# ADCduinoModule_Power.net
KiCad netlist of a schematic drawn in Altium Designer
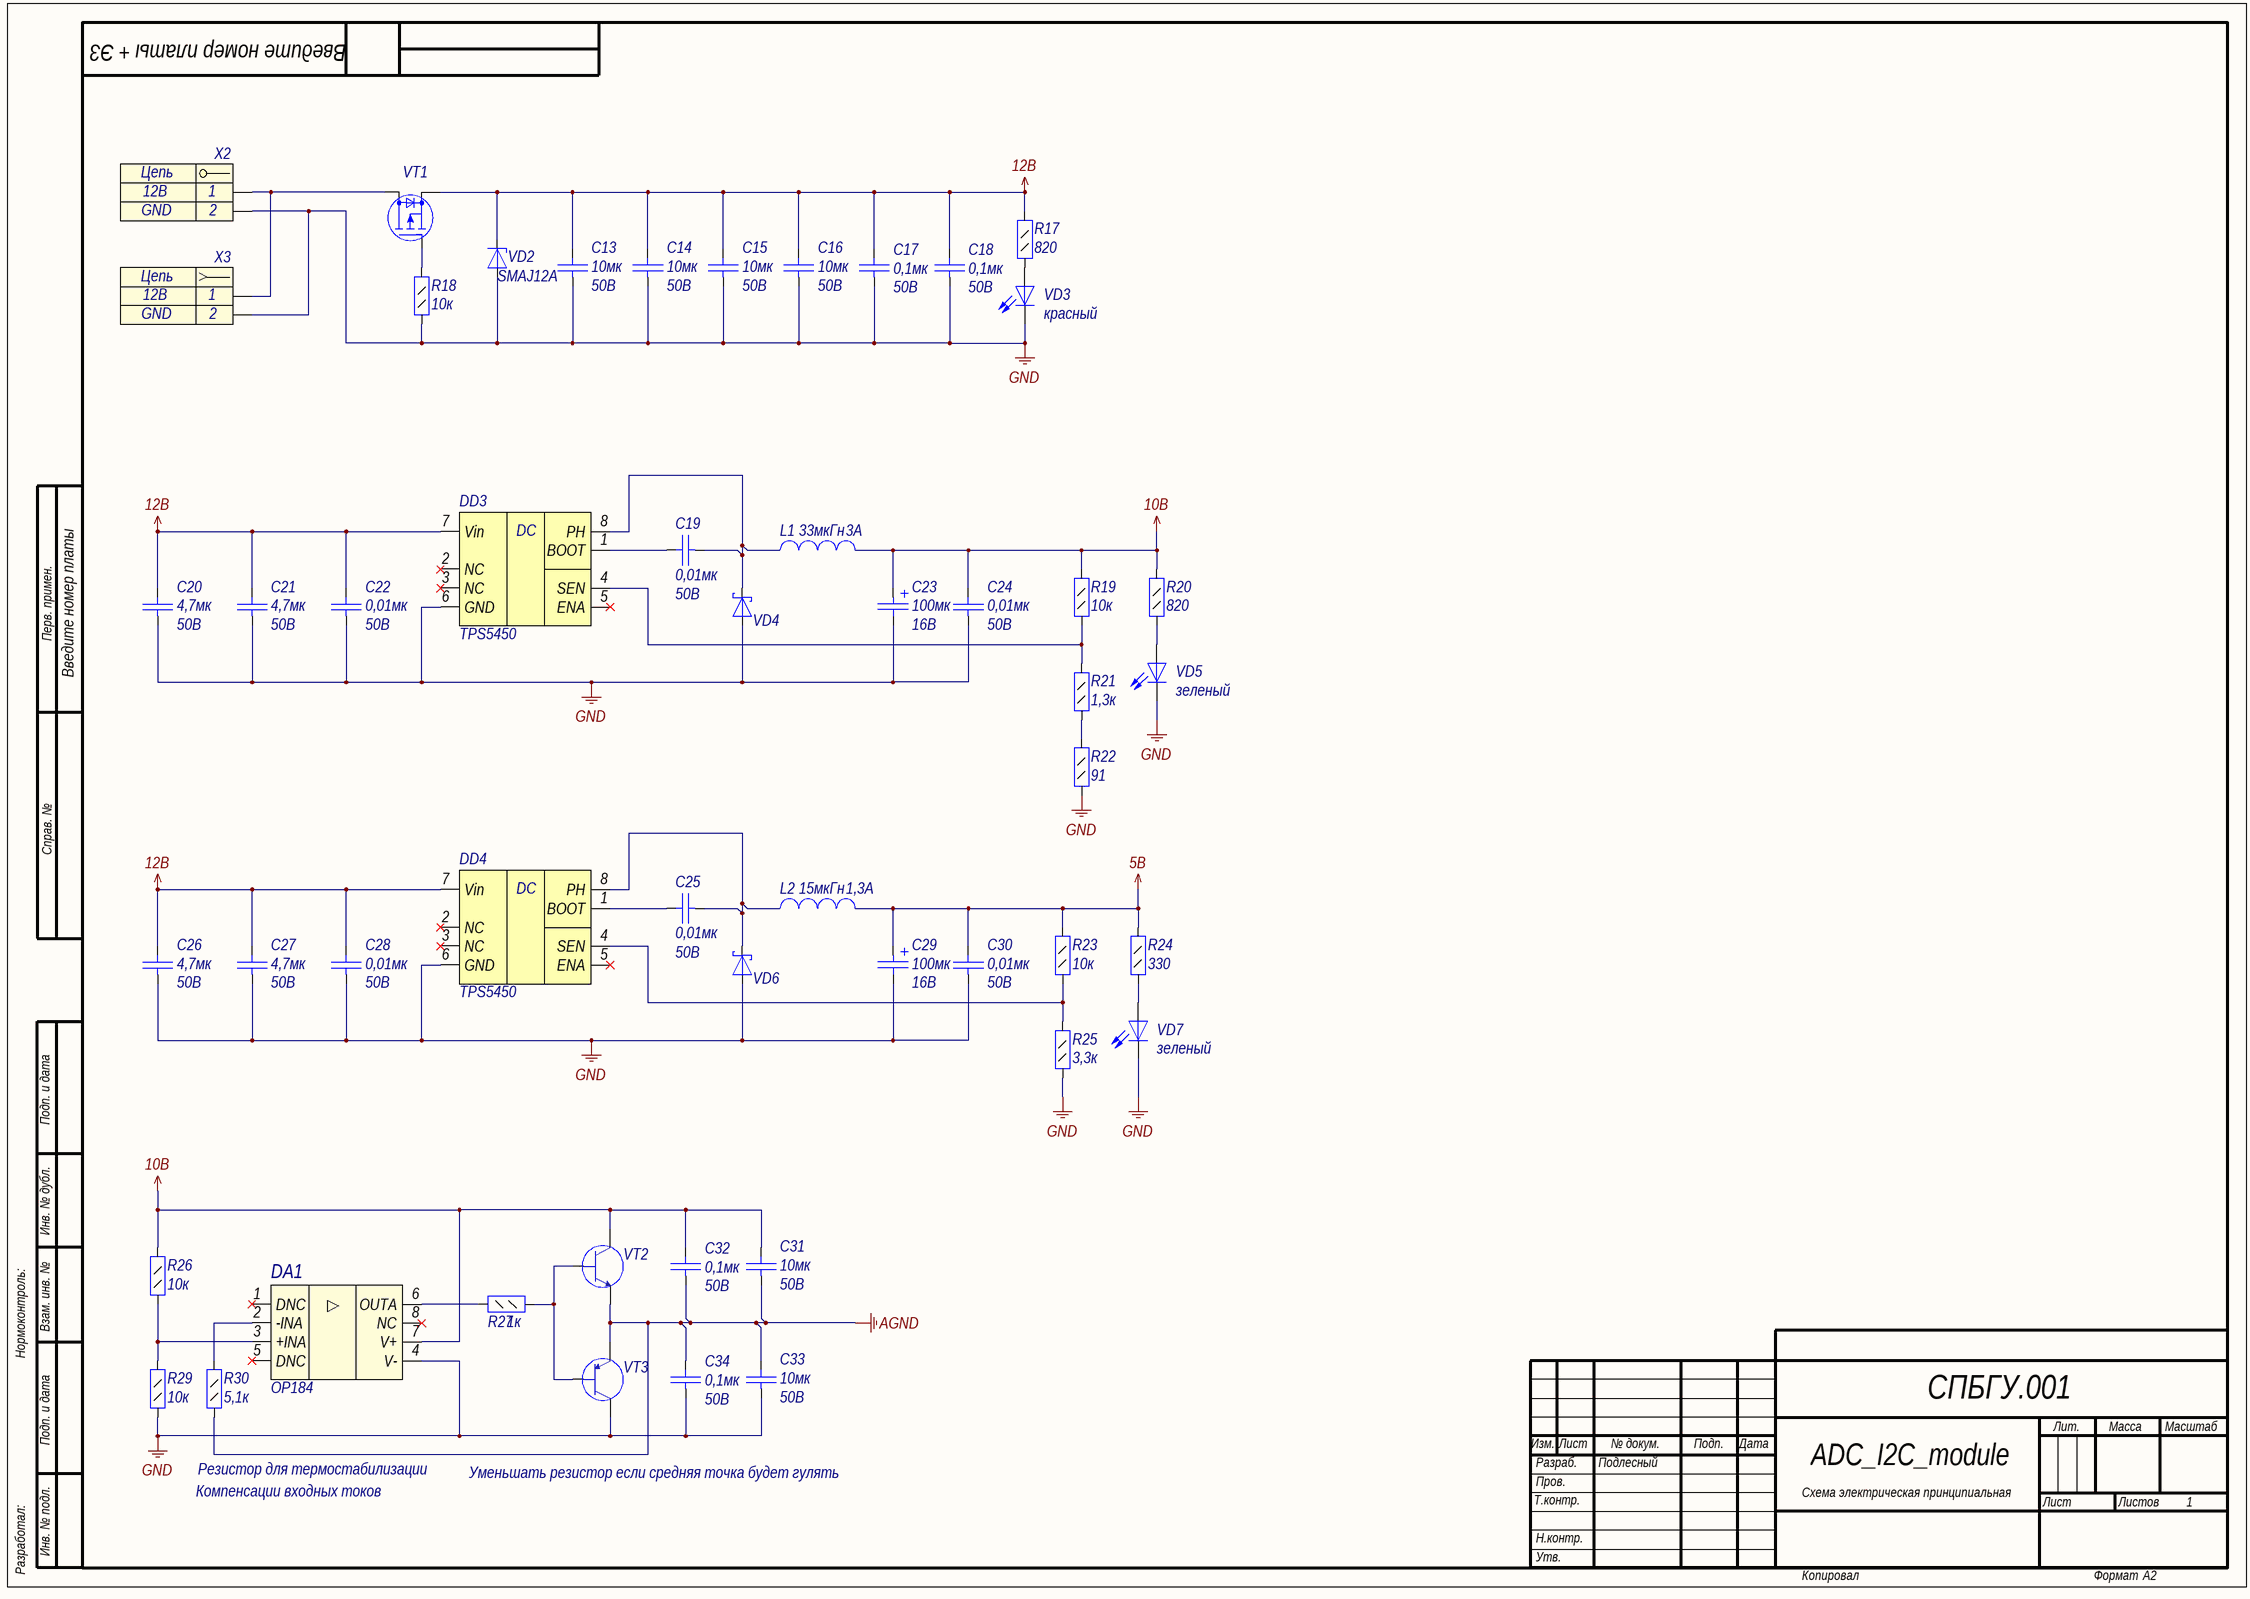
[diagram p0: ADCduinoModule_Power.SchDoc]

(export (version "E")
  (design (tool "Eeschema 10.0.6"))
  (components
    (comp (ref "C13")
      (value "10мк")
      (footprint "C1210")
      (description "Конденсатор")
      (fields
        (field (name "VOLTAGE") "50В")
        (field (name "PART NUMBER") "GRM32ER71H106K")
        (field (name "Comment") "Capacitor")
      )
      (libsource (lib "MOP44") (part "Capacitor"))
    )
    (comp (ref "C14")
      (value "10мк")
      (footprint "C1210")
      (description "Конденсатор")
      (fields
        (field (name "VOLTAGE") "50В")
        (field (name "PART NUMBER") "GRM32ER71H106K")
        (field (name "Comment") "Capacitor")
      )
      (libsource (lib "MOP44") (part "Capacitor"))
    )
    (comp (ref "C15")
      (value "10мк")
      (footprint "C1210")
      (description "Конденсатор")
      (fields
        (field (name "VOLTAGE") "50В")
        (field (name "PART NUMBER") "GRM32ER71H106K")
        (field (name "Comment") "Capacitor")
      )
      (libsource (lib "MOP44") (part "Capacitor"))
    )
    (comp (ref "C16")
      (value "10мк")
      (footprint "C1210")
      (description "Конденсатор")
      (fields
        (field (name "VOLTAGE") "50В")
        (field (name "PART NUMBER") "GRM32ER71H106K")
        (field (name "Comment") "Capacitor")
      )
      (libsource (lib "MOP44") (part "Capacitor"))
    )
    (comp (ref "C17")
      (value "0,1мк")
      (footprint "C0805")
      (description "Конденсатор")
      (fields
        (field (name "VOLTAGE") "50B")
        (field (name "PART NUMBER") "GRM21BR71H104K**")
        (field (name "Comment") "Capacitor")
      )
      (libsource (lib "MOP44") (part "Capacitor"))
    )
    (comp (ref "C18")
      (value "0,1мк")
      (footprint "C0805")
      (description "Конденсатор")
      (fields
        (field (name "VOLTAGE") "50B")
        (field (name "PART NUMBER") "GRM21BR71H104K**")
        (field (name "Comment") "Capacitor")
      )
      (libsource (lib "MOP44") (part "Capacitor"))
    )
    (comp (ref "C19")
      (value "0,01мк")
      (footprint "C0805")
      (description "Конденсатор")
      (fields
        (field (name "VOLTAGE") "50B")
        (field (name "PART NUMBER") "GRM216R71H103K")
        (field (name "Comment") "Capacitor")
      )
      (libsource (lib "MOP44") (part "Capacitor"))
    )
    (comp (ref "C20")
      (value "4,7мк")
      (footprint "C1206")
      (description "Конденсатор")
      (fields
        (field (name "VOLTAGE") "50В")
        (field (name "PART NUMBER") "GRM31CR71H475KA12L")
        (field (name "Comment") "Capacitor")
      )
      (libsource (lib "MOP44") (part "Capacitor"))
    )
    (comp (ref "C21")
      (value "4,7мк")
      (footprint "C1206")
      (description "Конденсатор")
      (fields
        (field (name "VOLTAGE") "50В")
        (field (name "PART NUMBER") "GRM31CR71H475KA12L")
        (field (name "Comment") "Capacitor")
      )
      (libsource (lib "MOP44") (part "Capacitor"))
    )
    (comp (ref "C22")
      (value "0,01мк")
      (footprint "C0805")
      (description "Конденсатор")
      (fields
        (field (name "VOLTAGE") "50B")
        (field (name "PART NUMBER") "GRM216R71H103K")
        (field (name "Comment") "Capacitor")
      )
      (libsource (lib "MOP44") (part "Capacitor"))
    )
    (comp (ref "C23")
      (value "100мк")
      (footprint "TANTAL CASE D")
      (description "Конденсатор полярный")
      (fields
        (field (name "VOLTAGE") "16В")
        (field (name "PART NUMBER") "293D107X9016D2TE3")
        (field (name "Comment") "Capacitor_pol")
      )
      (libsource (lib "MOP44") (part "Capacitor_pol"))
    )
    (comp (ref "C24")
      (value "0,01мк")
      (footprint "C0805")
      (description "Конденсатор")
      (fields
        (field (name "VOLTAGE") "50B")
        (field (name "PART NUMBER") "GRM216R71H103K")
        (field (name "Comment") "Capacitor")
      )
      (libsource (lib "MOP44") (part "Capacitor"))
    )
    (comp (ref "C25")
      (value "0,01мк")
      (footprint "C0805")
      (description "Конденсатор")
      (fields
        (field (name "VOLTAGE") "50B")
        (field (name "PART NUMBER") "GRM216R71H103K")
        (field (name "Comment") "Capacitor")
      )
      (libsource (lib "MOP44") (part "Capacitor"))
    )
    (comp (ref "C26")
      (value "4,7мк")
      (footprint "C1206")
      (description "Конденсатор")
      (fields
        (field (name "VOLTAGE") "50В")
        (field (name "PART NUMBER") "GRM31CR71H475KA12L")
        (field (name "Comment") "Capacitor")
      )
      (libsource (lib "MOP44") (part "Capacitor"))
    )
    (comp (ref "C27")
      (value "4,7мк")
      (footprint "C1206")
      (description "Конденсатор")
      (fields
        (field (name "VOLTAGE") "50В")
        (field (name "PART NUMBER") "GRM31CR71H475KA12L")
        (field (name "Comment") "Capacitor")
      )
      (libsource (lib "MOP44") (part "Capacitor"))
    )
    (comp (ref "C28")
      (value "0,01мк")
      (footprint "C0805")
      (description "Конденсатор")
      (fields
        (field (name "VOLTAGE") "50B")
        (field (name "PART NUMBER") "GRM216R71H103K")
        (field (name "Comment") "Capacitor")
      )
      (libsource (lib "MOP44") (part "Capacitor"))
    )
    (comp (ref "C29")
      (value "100мк")
      (footprint "TANTAL CASE D")
      (description "Конденсатор полярный")
      (fields
        (field (name "VOLTAGE") "16В")
        (field (name "PART NUMBER") "293D107X9016D2TE3")
        (field (name "Comment") "Capacitor_pol")
      )
      (libsource (lib "MOP44") (part "Capacitor_pol"))
    )
    (comp (ref "C30")
      (value "0,01мк")
      (footprint "C0805")
      (description "Конденсатор")
      (fields
        (field (name "VOLTAGE") "50B")
        (field (name "PART NUMBER") "GRM216R71H103K")
        (field (name "Comment") "Capacitor")
      )
      (libsource (lib "MOP44") (part "Capacitor"))
    )
    (comp (ref "C31")
      (value "10мк")
      (footprint "C1210")
      (description "Конденсатор")
      (fields
        (field (name "VOLTAGE") "50В")
        (field (name "PART NUMBER") "GRM32ER71H106K")
        (field (name "Comment") "Capacitor")
      )
      (libsource (lib "MOP44") (part "Capacitor"))
    )
    (comp (ref "C32")
      (value "0,1мк")
      (footprint "C0805")
      (description "Конденсатор")
      (fields
        (field (name "VOLTAGE") "50B")
        (field (name "PART NUMBER") "GRM21BR71H104K**")
        (field (name "Comment") "Capacitor")
      )
      (libsource (lib "MOP44") (part "Capacitor"))
    )
    (comp (ref "C33")
      (value "10мк")
      (footprint "C1210")
      (description "Конденсатор")
      (fields
        (field (name "VOLTAGE") "50В")
        (field (name "PART NUMBER") "GRM32ER71H106K")
        (field (name "Comment") "Capacitor")
      )
      (libsource (lib "MOP44") (part "Capacitor"))
    )
    (comp (ref "C34")
      (value "0,1мк")
      (footprint "C0805")
      (description "Конденсатор")
      (fields
        (field (name "VOLTAGE") "50B")
        (field (name "PART NUMBER") "GRM21BR71H104K**")
        (field (name "Comment") "Capacitor")
      )
      (libsource (lib "MOP44") (part "Capacitor"))
    )
    (comp (ref "DA1")
      (value "OP184")
      (footprint "SO8")
      (description "Precision Rail-to-Rail\r\nInput and Output Operational Amplifiers")
      (fields (field (name "PART NUMBER") "OP184ESZ"))
      (libsource (lib "MOP44") (part "OP184"))
    )
    (comp (ref "DD3")
      (value "TPS5450")
      (footprint "SO Powerpad8")
      (description "5-A, Wide Input Range, Step-Down Converter")
      (fields (field (name "MANUFACTURER") "Texas Instruments"))
      (libsource (lib "MOP44") (part "TPS5450"))
    )
    (comp (ref "DD4")
      (value "TPS5450")
      (footprint "SO Powerpad8")
      (description "5-A, Wide Input Range, Step-Down Converter")
      (fields (field (name "MANUFACTURER") "Texas Instruments"))
      (libsource (lib "MOP44") (part "TPS5450"))
    )
    (comp (ref "L1")
      (value "33мкГн")
      (footprint "IND_12.8x12.8")
      (description "EMI Suppression Filter")
      (fields
        (field (name "RATED CURRENT") "3A")
        (field (name "PART NUMBER") "B82477G4333M000")
        (field (name "Comment") "Inductor")
      )
      (libsource (lib "MOP44") (part "Inductor"))
    )
    (comp (ref "L2")
      (value "15мкГн")
      (footprint "SDR0604")
      (description "EMI Suppression Filter")
      (fields
        (field (name "RATED CURRENT") "1,3A")
        (field (name "PART NUMBER") "SDR0604- 150YL")
        (field (name "Comment") "Inductor")
      )
      (libsource (lib "MOP44") (part "Inductor"))
    )
    (comp (ref "R17")
      (value "820")
      (footprint "R0805")
      (description "Резистор")
      (fields (field (name "PART NUMBER") "RC0805FR-07820RL") (field (name "POWER") "0,125Вт"))
      (libsource (lib "MOP44") (part "Resistor_0,125Вт"))
    )
    (comp (ref "R18")
      (value "10к")
      (footprint "R0805")
      (description "Резистор")
      (fields (field (name "PART NUMBER") "RC0805FR-0710KL") (field (name "POWER") "0,125Вт"))
      (libsource (lib "MOP44") (part "Resistor_0,125Вт"))
    )
    (comp (ref "R19")
      (value "10к")
      (footprint "R0805")
      (description "Резистор")
      (fields (field (name "PART NUMBER") "RC0805FR-0710KL") (field (name "POWER") "0,125Вт"))
      (libsource (lib "MOP44") (part "Resistor_0,125Вт"))
    )
    (comp (ref "R20")
      (value "820")
      (footprint "R0805")
      (description "Резистор")
      (fields (field (name "PART NUMBER") "RC0805FR-07820RL") (field (name "POWER") "0,125Вт"))
      (libsource (lib "MOP44") (part "Resistor_0,125Вт"))
    )
    (comp (ref "R21")
      (value "1,3к")
      (footprint "R0805")
      (description "Резистор")
      (fields (field (name "PART NUMBER") "RC0805FR-071K3") (field (name "POWER") "0,125Вт"))
      (libsource (lib "MOP44") (part "Resistor_0,125Вт"))
    )
    (comp (ref "R22")
      (value "91")
      (footprint "R0805")
      (description "Резистор")
      (fields (field (name "PART NUMBER") "RC0805FR-0791RL") (field (name "POWER") "0,125Вт"))
      (libsource (lib "MOP44") (part "Resistor_0,125Вт"))
    )
    (comp (ref "R23")
      (value "10к")
      (footprint "R0805")
      (description "Резистор")
      (fields (field (name "PART NUMBER") "RC0805FR-0710KL") (field (name "POWER") "0,125Вт"))
      (libsource (lib "MOP44") (part "Resistor_0,125Вт"))
    )
    (comp (ref "R24")
      (value "330")
      (footprint "R0805")
      (description "Резистор")
      (fields (field (name "PART NUMBER") "RC0805FR-07330RL") (field (name "POWER") "0,125Вт"))
      (libsource (lib "MOP44") (part "Resistor_0,125Вт"))
    )
    (comp (ref "R25")
      (value "3,3к")
      (footprint "R0805")
      (description "Резистор")
      (fields (field (name "PART NUMBER") "RC0805FR-072K3") (field (name "POWER") "0,125Вт"))
      (libsource (lib "MOP44") (part "Resistor_0,125Вт"))
    )
    (comp (ref "R26")
      (value "10к")
      (footprint "R0805")
      (description "Резистор")
      (fields (field (name "PART NUMBER") "RC0805FR-0710KL") (field (name "POWER") "0,125Вт"))
      (libsource (lib "MOP44") (part "Resistor_0,125Вт"))
    )
    (comp (ref "R27")
      (value "1к")
      (footprint "R0805")
      (description "Резистор")
      (fields (field (name "PART NUMBER") "RC0805FR-071KL") (field (name "POWER") "0,125Вт"))
      (libsource (lib "") (part "Resistor_0,125Вт_1"))
    )
    (comp (ref "R29")
      (value "10к")
      (footprint "R0805")
      (description "Резистор")
      (fields (field (name "PART NUMBER") "RC0805FR-0710KL") (field (name "POWER") "0,125Вт"))
      (libsource (lib "MOP44") (part "Resistor_0,125Вт"))
    )
    (comp (ref "R30")
      (value "5,1к")
      (footprint "R0805")
      (description "Резистор")
      (fields (field (name "PART NUMBER") "RC0805FR-075K1") (field (name "POWER") "0,125Вт"))
      (libsource (lib "MOP44") (part "Resistor_0,125Вт"))
    )
    (comp (ref "VD2")
      (value "DiodeZener")
      (footprint "SMA")
      (description "Cтабилитрон (лавинный выпрямительный диод) односторонний")
      (fields (field (name "PART NUMBER") "SMAJ12A"))
      (libsource (lib "MOP44") (part "DiodeZener"))
    )
    (comp (ref "VD3")
      (value "красный")
      (footprint "L_0805")
      (description "Светодиод")
      (fields (field (name "PART NUMBER") "KP-2012EC"))
      (libsource (lib "MOP44") (part "LED"))
    )
    (comp (ref "VD4")
      (value "DiodeSchottky")
      (footprint "SMA")
      (description "Диод Шоттки")
      (fields (field (name "PART NUMBER") "SK34A"))
      (libsource (lib "MOP44") (part "DiodeSchottky"))
    )
    (comp (ref "VD5")
      (value "зеленый")
      (footprint "L_0805")
      (description "Светодиод")
      (fields (field (name "PART NUMBER") "KP-2012MGC"))
      (libsource (lib "MOP44") (part "LED"))
    )
    (comp (ref "VD6")
      (value "DiodeSchottky")
      (footprint "SMA")
      (description "Диод Шоттки")
      (fields (field (name "PART NUMBER") "SK34A"))
      (libsource (lib "MOP44") (part "DiodeSchottky"))
    )
    (comp (ref "VD7")
      (value "зеленый")
      (footprint "L_0805")
      (description "Светодиод")
      (fields (field (name "PART NUMBER") "KP-2012MGC"))
      (libsource (lib "MOP44") (part "LED"))
    )
    (comp (ref "VT1")
      (value "P-MOSFET")
      (footprint "DPAK")
      (description "N-MOSFET")
      (fields (field (name "PART NUMBER") "FDD6637") (field (name "MANUFACTURER") "Fairchild Semiconductor"))
      (libsource (lib "MOP44") (part "P-MOSFET"))
    )
    (comp (ref "VT2")
      (value "BJT NPN")
      (footprint "SOT-223")
      (fields (field (name "POWER") "2Вт") (field (name "PART NUMBER") "PBSS4540Z.115"))
      (libsource (lib "MOP44") (part "BJT NPN"))
    )
    (comp (ref "VT3")
      (value "BJT PNP")
      (footprint "SOT-223")
      (fields (field (name "POWER") "2Вт") (field (name "PART NUMBER") "PBSS5540Z.115"))
      (libsource (lib "MOP44") (part "BJT PNP"))
    )
    (comp (ref "X2")
      (value "Header_2_trm")
      (footprint "TERMINAL-2WAY-3.5MM")
      (description "Разъем - 2 конт. клеммник")
      (libsource (lib "MOP44") (part "Header_2_trm"))
    )
    (comp (ref "X3")
      (value "Header_2_sct")
      (footprint "DS-210")
      (description "Разъем - 2 конт. розетка")
      (fields (field (name "PART NUMBER") "DS-210B(PBT)(NB)"))
      (libsource (lib "MOP44") (part "Header_2_sct"))
    )
  )
  (nets
    (net (code "1") (name "5B") (class "Default")
      (node (ref "C29") (pin "1") (pinfunction "1_1") (pintype "passive"))
      (node (ref "C30") (pin "2") (pinfunction "2_2") (pintype "passive"))
      (node (ref "L2") (pin "2") (pinfunction "2_2") (pintype "passive"))
      (node (ref "R23") (pin "2") (pinfunction "2_2") (pintype "passive"))
      (node (ref "R24") (pin "2") (pinfunction "2_2") (pintype "passive"))
    )
    (net (code "2") (name "10B") (class "Default")
      (node (ref "C23") (pin "1") (pinfunction "1_1") (pintype "passive"))
      (node (ref "C24") (pin "2") (pinfunction "2_2") (pintype "passive"))
      (node (ref "C31") (pin "2") (pinfunction "2_2") (pintype "passive"))
      (node (ref "C32") (pin "2") (pinfunction "2_2") (pintype "passive"))
      (node (ref "DA1") (pin "7") (pinfunction "V+_7") (pintype "power_in"))
      (node (ref "L1") (pin "2") (pinfunction "2_2") (pintype "passive"))
      (node (ref "R19") (pin "2") (pinfunction "2_2") (pintype "passive"))
      (node (ref "R20") (pin "2") (pinfunction "2_2") (pintype "passive"))
      (node (ref "R26") (pin "2") (pinfunction "2_2") (pintype "passive"))
      (node (ref "VT2") (pin "3") (pinfunction "3_3") (pintype "passive"))
    )
    (net (code "3") (name "12B") (class "Default")
      (node (ref "C13") (pin "2") (pinfunction "2_2") (pintype "passive"))
      (node (ref "C14") (pin "2") (pinfunction "2_2") (pintype "passive"))
      (node (ref "C15") (pin "2") (pinfunction "2_2") (pintype "passive"))
      (node (ref "C16") (pin "2") (pinfunction "2_2") (pintype "passive"))
      (node (ref "C17") (pin "2") (pinfunction "2_2") (pintype "passive"))
      (node (ref "C18") (pin "2") (pinfunction "2_2") (pintype "passive"))
      (node (ref "C20") (pin "2") (pinfunction "2_2") (pintype "passive"))
      (node (ref "C21") (pin "2") (pinfunction "2_2") (pintype "passive"))
      (node (ref "C22") (pin "2") (pinfunction "2_2") (pintype "passive"))
      (node (ref "C26") (pin "2") (pinfunction "2_2") (pintype "passive"))
      (node (ref "C27") (pin "2") (pinfunction "2_2") (pintype "passive"))
      (node (ref "C28") (pin "2") (pinfunction "2_2") (pintype "passive"))
      (node (ref "DD3") (pin "7") (pinfunction "Vin_7") (pintype "passive"))
      (node (ref "DD4") (pin "7") (pinfunction "Vin_7") (pintype "passive"))
      (node (ref "R17") (pin "2") (pinfunction "2_2") (pintype "passive"))
      (node (ref "VD2") (pin "1") (pinfunction "K_1") (pintype "passive"))
      (node (ref "VT1") (pin "3") (pinfunction "S_3") (pintype "passive"))
    )
    (net (code "4") (name "AGND") (class "Default")
      (node (ref "C31") (pin "1") (pinfunction "1_1") (pintype "passive"))
      (node (ref "C32") (pin "1") (pinfunction "1_1") (pintype "passive"))
      (node (ref "C33") (pin "2") (pinfunction "2_2") (pintype "passive"))
      (node (ref "C34") (pin "2") (pinfunction "2_2") (pintype "passive"))
      (node (ref "R30") (pin "1") (pinfunction "1_1") (pintype "passive"))
      (node (ref "VT2") (pin "2") (pinfunction "2_2") (pintype "passive"))
      (node (ref "VT3") (pin "2") (pinfunction "2_2") (pintype "passive"))
    )
    (net (code "5") (name "GND") (class "Default")
      (node (ref "C13") (pin "1") (pinfunction "1_1") (pintype "passive"))
      (node (ref "C14") (pin "1") (pinfunction "1_1") (pintype "passive"))
      (node (ref "C15") (pin "1") (pinfunction "1_1") (pintype "passive"))
      (node (ref "C16") (pin "1") (pinfunction "1_1") (pintype "passive"))
      (node (ref "C17") (pin "1") (pinfunction "1_1") (pintype "passive"))
      (node (ref "C18") (pin "1") (pinfunction "1_1") (pintype "passive"))
      (node (ref "C20") (pin "1") (pinfunction "1_1") (pintype "passive"))
      (node (ref "C21") (pin "1") (pinfunction "1_1") (pintype "passive"))
      (node (ref "C22") (pin "1") (pinfunction "1_1") (pintype "passive"))
      (node (ref "C23") (pin "2") (pinfunction "2_2") (pintype "passive"))
      (node (ref "C24") (pin "1") (pinfunction "1_1") (pintype "passive"))
      (node (ref "C26") (pin "1") (pinfunction "1_1") (pintype "passive"))
      (node (ref "C27") (pin "1") (pinfunction "1_1") (pintype "passive"))
      (node (ref "C28") (pin "1") (pinfunction "1_1") (pintype "passive"))
      (node (ref "C29") (pin "2") (pinfunction "2_2") (pintype "passive"))
      (node (ref "C30") (pin "1") (pinfunction "1_1") (pintype "passive"))
      (node (ref "C33") (pin "1") (pinfunction "1_1") (pintype "passive"))
      (node (ref "C34") (pin "1") (pinfunction "1_1") (pintype "passive"))
      (node (ref "DA1") (pin "4") (pinfunction "V-_4") (pintype "power_in"))
      (node (ref "DD3") (pin "6") (pinfunction "GND_6") (pintype "passive"))
      (node (ref "DD4") (pin "6") (pinfunction "GND_6") (pintype "passive"))
      (node (ref "R18") (pin "1") (pinfunction "1_1") (pintype "passive"))
      (node (ref "R22") (pin "1") (pinfunction "1_1") (pintype "passive"))
      (node (ref "R25") (pin "1") (pinfunction "1_1") (pintype "passive"))
      (node (ref "R29") (pin "1") (pinfunction "1_1") (pintype "passive"))
      (node (ref "VD2") (pin "2") (pinfunction "A_2") (pintype "passive"))
      (node (ref "VD3") (pin "1") (pinfunction "K_1") (pintype "passive"))
      (node (ref "VD4") (pin "2") (pinfunction "A_2") (pintype "passive"))
      (node (ref "VD5") (pin "1") (pinfunction "K_1") (pintype "passive"))
      (node (ref "VD6") (pin "2") (pinfunction "A_2") (pintype "passive"))
      (node (ref "VD7") (pin "1") (pinfunction "K_1") (pintype "passive"))
      (node (ref "VT3") (pin "3") (pinfunction "3_3") (pintype "passive"))
      (node (ref "X2") (pin "2") (pinfunction "2_2") (pintype "passive"))
      (node (ref "X3") (pin "2") (pinfunction "2_2") (pintype "passive"))
    )
    (net (code "6") (name "Net-(DA1-+INA)") (class "Default")
      (node (ref "DA1") (pin "3") (pinfunction "+INA_3") (pintype "power_in"))
      (node (ref "R26") (pin "1") (pinfunction "1_1") (pintype "passive"))
      (node (ref "R29") (pin "2") (pinfunction "2_2") (pintype "passive"))
    )
    (net (code "7") (name "Net-(DA1--INA)") (class "Default")
      (node (ref "DA1") (pin "2") (pinfunction "-INA_2") (pintype "power_in"))
      (node (ref "R30") (pin "2") (pinfunction "2_2") (pintype "passive"))
    )
    (net (code "8") (name "Net-(DA1-OUTA)") (class "Default")
      (node (ref "DA1") (pin "6") (pinfunction "OUTA_6") (pintype "power_in"))
      (node (ref "R27") (pin "1") (pinfunction "1_1") (pintype "passive"))
    )
    (net (code "9") (name "Net-(DD3-BOOT)") (class "Default")
      (node (ref "C19") (pin "2") (pinfunction "2_2") (pintype "passive"))
      (node (ref "DD3") (pin "1") (pinfunction "BOOT_1") (pintype "passive"))
    )
    (net (code "10") (name "Net-(DD3-PH)") (class "Default")
      (node (ref "C19") (pin "1") (pinfunction "1_1") (pintype "passive"))
      (node (ref "DD3") (pin "8") (pinfunction "PH_8") (pintype "passive"))
      (node (ref "L1") (pin "1") (pinfunction "1_1") (pintype "passive"))
      (node (ref "VD4") (pin "1") (pinfunction "K_1") (pintype "passive"))
    )
    (net (code "11") (name "Net-(DD3-SEN)") (class "Default")
      (node (ref "DD3") (pin "4") (pinfunction "SEN_4") (pintype "passive"))
      (node (ref "R19") (pin "1") (pinfunction "1_1") (pintype "passive"))
      (node (ref "R21") (pin "2") (pinfunction "2_2") (pintype "passive"))
    )
    (net (code "12") (name "Net-(DD4-BOOT)") (class "Default")
      (node (ref "C25") (pin "2") (pinfunction "2_2") (pintype "passive"))
      (node (ref "DD4") (pin "1") (pinfunction "BOOT_1") (pintype "passive"))
    )
    (net (code "13") (name "Net-(DD4-PH)") (class "Default")
      (node (ref "C25") (pin "1") (pinfunction "1_1") (pintype "passive"))
      (node (ref "DD4") (pin "8") (pinfunction "PH_8") (pintype "passive"))
      (node (ref "L2") (pin "1") (pinfunction "1_1") (pintype "passive"))
      (node (ref "VD6") (pin "1") (pinfunction "K_1") (pintype "passive"))
    )
    (net (code "14") (name "Net-(DD4-SEN)") (class "Default")
      (node (ref "DD4") (pin "4") (pinfunction "SEN_4") (pintype "passive"))
      (node (ref "R23") (pin "1") (pinfunction "1_1") (pintype "passive"))
      (node (ref "R25") (pin "2") (pinfunction "2_2") (pintype "passive"))
    )
    (net (code "15") (name "Net-(R21-Pad1)") (class "Default")
      (node (ref "R21") (pin "1") (pinfunction "1_1") (pintype "passive"))
      (node (ref "R22") (pin "2") (pinfunction "2_2") (pintype "passive"))
    )
    (net (code "16") (name "Net-(R27-Pad2)") (class "Default")
      (node (ref "R27") (pin "2") (pinfunction "2_2") (pintype "passive"))
      (node (ref "VT2") (pin "1") (pinfunction "1_1") (pintype "passive"))
      (node (ref "VT3") (pin "1") (pinfunction "1_1") (pintype "passive"))
    )
    (net (code "17") (name "Net-(VD3-A)") (class "Default")
      (node (ref "R17") (pin "1") (pinfunction "1_1") (pintype "passive"))
      (node (ref "VD3") (pin "2") (pinfunction "A_2") (pintype "passive"))
    )
    (net (code "18") (name "Net-(VD5-A)") (class "Default")
      (node (ref "R20") (pin "1") (pinfunction "1_1") (pintype "passive"))
      (node (ref "VD5") (pin "2") (pinfunction "A_2") (pintype "passive"))
    )
    (net (code "19") (name "Net-(VD7-A)") (class "Default")
      (node (ref "R24") (pin "1") (pinfunction "1_1") (pintype "passive"))
      (node (ref "VD7") (pin "2") (pinfunction "A_2") (pintype "passive"))
    )
    (net (code "20") (name "Net-(VT1-D)") (class "Default")
      (node (ref "VT1") (pin "2") (pinfunction "D_2") (pintype "passive"))
      (node (ref "X2") (pin "1") (pinfunction "1_1") (pintype "passive"))
      (node (ref "X3") (pin "1") (pinfunction "1_1") (pintype "passive"))
    )
    (net (code "21") (name "Net-(VT1-G)") (class "Default")
      (node (ref "R18") (pin "2") (pinfunction "2_2") (pintype "passive"))
      (node (ref "VT1") (pin "1") (pinfunction "G_1") (pintype "passive"))
    )
    (net (code "22") (name "unconnected-(DA1-DNC-Pad1)") (class "Default")
      (node (ref "DA1") (pin "1") (pinfunction "DNC_1") (pintype "power_in+no_connect"))
    )
    (net (code "23") (name "unconnected-(DA1-DNC-Pad5)") (class "Default")
      (node (ref "DA1") (pin "5") (pinfunction "DNC_5") (pintype "power_in+no_connect"))
    )
    (net (code "24") (name "unconnected-(DA1-NC-Pad8)") (class "Default")
      (node (ref "DA1") (pin "8") (pinfunction "NC_8") (pintype "power_in+no_connect"))
    )
    (net (code "25") (name "unconnected-(DD3-ENA-Pad5)") (class "Default")
      (node (ref "DD3") (pin "5") (pinfunction "ENA_5") (pintype "passive+no_connect"))
    )
    (net (code "26") (name "unconnected-(DD3-NC-Pad2)") (class "Default")
      (node (ref "DD3") (pin "2") (pinfunction "NC_2") (pintype "passive+no_connect"))
    )
    (net (code "27") (name "unconnected-(DD3-NC-Pad3)") (class "Default")
      (node (ref "DD3") (pin "3") (pinfunction "NC_3") (pintype "passive+no_connect"))
    )
    (net (code "28") (name "unconnected-(DD4-ENA-Pad5)") (class "Default")
      (node (ref "DD4") (pin "5") (pinfunction "ENA_5") (pintype "passive+no_connect"))
    )
    (net (code "29") (name "unconnected-(DD4-NC-Pad2)") (class "Default")
      (node (ref "DD4") (pin "2") (pinfunction "NC_2") (pintype "passive+no_connect"))
    )
    (net (code "30") (name "unconnected-(DD4-NC-Pad3)") (class "Default")
      (node (ref "DD4") (pin "3") (pinfunction "NC_3") (pintype "passive+no_connect"))
    )
  )
)
